# master.net
KiCad netlist of a schematic drawn in Altium Designer
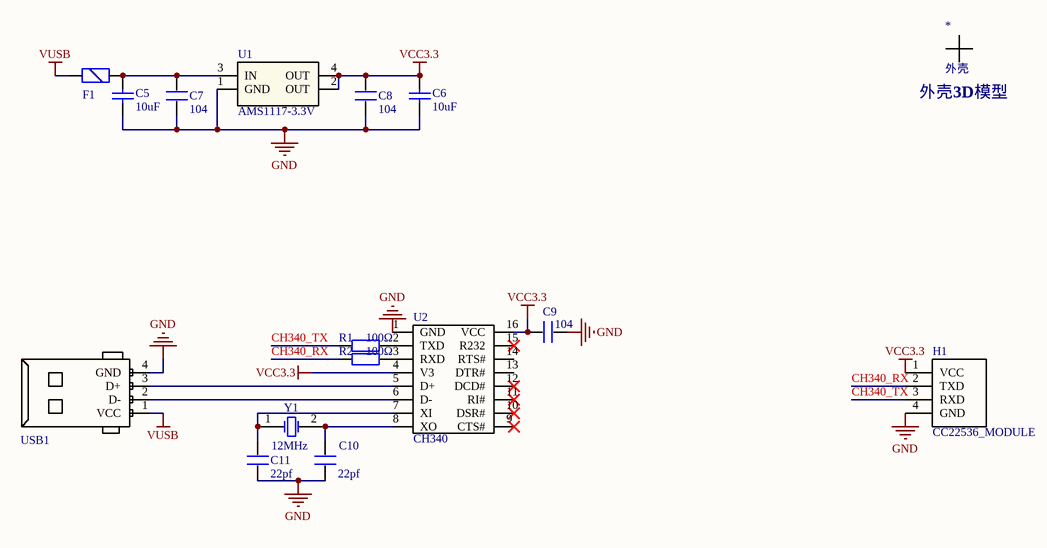
[diagram p0: master.SchDoc]

(export (version "E")
  (design (tool "Eeschema 10.0.6"))
  (components
    (comp (ref "*") (value "外壳") (footprint "MYLIB:接收端外壳") (libsource (lib "mylib") (part "外壳")))
    (comp (ref "C5")
      (value "10uF")
      (footprint "0805_C")
      (description "贴片电容")
      (libsource (lib "嘉立创库") (part "0805 2.2uF (225) 20% 50V"))
    )
    (comp (ref "C6")
      (value "10uF")
      (footprint "0805_C")
      (description "贴片电容")
      (libsource (lib "嘉立创库") (part "0805 2.2uF (225) 20% 50V"))
    )
    (comp (ref "C7")
      (value "104")
      (footprint "嘉立创库:0603_C")
      (libsource (lib "WarShip V3 STM32103封装库") (part "C"))
    )
    (comp (ref "C8")
      (value "104")
      (footprint "嘉立创库:0603_C")
      (libsource (lib "WarShip V3 STM32103封装库") (part "C"))
    )
    (comp (ref "C9")
      (value "104")
      (footprint "嘉立创库:0603_C")
      (libsource (lib "WarShip V3 STM32103封装库") (part "C"))
    )
    (comp (ref "C10")
      (value "22pf")
      (footprint "嘉立创库:0603_C")
      (libsource (lib "WarShip V3 STM32103封装库") (part "C"))
    )
    (comp (ref "C11")
      (value "22pf")
      (footprint "嘉立创库:0603_C")
      (libsource (lib "WarShip V3 STM32103封装库") (part "C"))
    )
    (comp (ref "F1") (value "F1") (footprint "MYLIB:Fuse1210") (libsource (lib "mylib") (part "Fuse")))
    (comp (ref "H1")
      (value "CC22536_MODULE")
      (footprint "WARSHIP:HDR1X4")
      (libsource (lib "mylib") (part "CC22536_MODULE"))
    )
    (comp (ref "R1")
      (value "100Ω")
      (footprint "0603_R")
      (description "贴片电阻")
      (libsource (lib "嘉立创库") (part "0603 1.1KΩ (1101) 1%"))
    )
    (comp (ref "R2")
      (value "100Ω")
      (footprint "0603_R")
      (description "贴片电阻")
      (libsource (lib "嘉立创库") (part "0603 1.1KΩ (1101) 1%"))
    )
    (comp (ref "U1")
      (value "AMS1117-3.3V")
      (footprint "AMS1117_S0T89")
      (libsource (lib "mylib") (part "AMS1117"))
    )
    (comp (ref "U2") (value "CH340") (footprint "3D common:SOP16") (libsource (lib "mylib") (part "CH340")))
    (comp (ref "USB1") (value "USB") (footprint "MYLIB:USB-211") (libsource (lib "mylib") (part "USB公头A")))
    (comp (ref "Y1")
      (value "12MHz")
      (footprint "3D_1:XTAL-49/S_N")
      (description "Crystal Oscillator")
      (fields (field (name "PUBLISHER") "Altium Limited"))
      (libsource (lib "WarShip V3 STM32103封装库") (part "XTAL"))
    )
  )
  (nets
    (net (code "1") (name "/CH340_RX") (class "Default")
      (node (ref "H1") (pin "2") (pinfunction "TXD_2") (pintype "passive"))
      (node (ref "R2") (pin "2") (pinfunction "2_2") (pintype "passive"))
    )
    (net (code "2") (name "/CH340_TX") (class "Default")
      (node (ref "H1") (pin "3") (pinfunction "RXD_3") (pintype "passive"))
      (node (ref "R1") (pin "2") (pinfunction "2_2") (pintype "passive"))
    )
    (net (code "3") (name "GND") (class "Default")
      (node (ref "C10") (pin "2") (pintype "passive"))
      (node (ref "C11") (pin "1") (pintype "passive"))
      (node (ref "C5") (pin "1") (pinfunction "1_1") (pintype "passive"))
      (node (ref "C6") (pin "1") (pinfunction "1_1") (pintype "passive"))
      (node (ref "C7") (pin "2") (pintype "passive"))
      (node (ref "C8") (pin "2") (pintype "passive"))
      (node (ref "C9") (pin "1") (pintype "passive"))
      (node (ref "H1") (pin "4") (pinfunction "GND_4") (pintype "passive"))
      (node (ref "U1") (pin "1") (pinfunction "GND_1") (pintype "passive"))
      (node (ref "U2") (pin "1") (pinfunction "GND_1") (pintype "passive"))
      (node (ref "USB1") (pin "4") (pinfunction "GND_4") (pintype "passive"))
    )
    (net (code "4") (name "Net-(U1-IN)") (class "Default")
      (node (ref "C5") (pin "2") (pinfunction "2_2") (pintype "passive"))
      (node (ref "C7") (pin "1") (pintype "passive"))
      (node (ref "F1") (pin "1") (pinfunction "1_1") (pintype "passive"))
      (node (ref "U1") (pin "3") (pinfunction "IN_3") (pintype "passive"))
    )
    (net (code "5") (name "Net-(U2-D+)") (class "Default")
      (node (ref "U2") (pin "5") (pinfunction "D+_5") (pintype "passive"))
      (node (ref "USB1") (pin "3") (pinfunction "D+_3") (pintype "passive"))
    )
    (net (code "6") (name "Net-(U2-D-)") (class "Default")
      (node (ref "U2") (pin "6") (pinfunction "D-_6") (pintype "passive"))
      (node (ref "USB1") (pin "2") (pinfunction "D-_2") (pintype "passive"))
    )
    (net (code "7") (name "Net-(U2-RXD)") (class "Default")
      (node (ref "R2") (pin "1") (pinfunction "1_1") (pintype "passive"))
      (node (ref "U2") (pin "3") (pinfunction "RXD_3") (pintype "passive"))
    )
    (net (code "8") (name "Net-(U2-TXD)") (class "Default")
      (node (ref "R1") (pin "1") (pinfunction "1_1") (pintype "passive"))
      (node (ref "U2") (pin "2") (pinfunction "TXD_2") (pintype "passive"))
    )
    (net (code "9") (name "Net-(U2-XI)") (class "Default")
      (node (ref "C11") (pin "2") (pintype "passive"))
      (node (ref "U2") (pin "7") (pinfunction "XI_7") (pintype "passive"))
      (node (ref "Y1") (pin "1") (pinfunction "OSC1_1") (pintype "passive"))
    )
    (net (code "10") (name "Net-(U2-XO)") (class "Default")
      (node (ref "C10") (pin "1") (pintype "passive"))
      (node (ref "U2") (pin "8") (pinfunction "XO_8") (pintype "passive"))
      (node (ref "Y1") (pin "2") (pinfunction "OSC2_2") (pintype "passive"))
    )
    (net (code "11") (name "VCC3.3") (class "Default")
      (node (ref "C6") (pin "2") (pinfunction "2_2") (pintype "passive"))
      (node (ref "C8") (pin "1") (pintype "passive"))
      (node (ref "C9") (pin "2") (pintype "passive"))
      (node (ref "H1") (pin "1") (pinfunction "VCC_1") (pintype "passive"))
      (node (ref "U1") (pin "2") (pinfunction "OUT_2") (pintype "passive"))
      (node (ref "U1") (pin "4") (pinfunction "OUT_4") (pintype "passive"))
      (node (ref "U2") (pin "16") (pinfunction "VCC_16") (pintype "passive"))
      (node (ref "U2") (pin "4") (pinfunction "V3_4") (pintype "passive"))
    )
    (net (code "12") (name "VUSB") (class "Default")
      (node (ref "F1") (pin "2") (pinfunction "2_2") (pintype "passive"))
      (node (ref "USB1") (pin "1") (pinfunction "VCC_1") (pintype "passive"))
    )
    (net (code "13") (name "unconnected-(U2-CTS#-Pad9)") (class "Default")
      (node (ref "U2") (pin "9") (pinfunction "CTS#_9") (pintype "passive+no_connect"))
    )
    (net (code "14") (name "unconnected-(U2-DCD#-Pad12)") (class "Default")
      (node (ref "U2") (pin "12") (pinfunction "DCD#_12") (pintype "passive+no_connect"))
    )
    (net (code "15") (name "unconnected-(U2-DSR#-Pad10)") (class "Default")
      (node (ref "U2") (pin "10") (pinfunction "DSR#_10") (pintype "passive+no_connect"))
    )
    (net (code "16") (name "unconnected-(U2-DTR#-Pad13)") (class "Default")
      (node (ref "U2") (pin "13") (pinfunction "DTR#_13") (pintype "passive"))
    )
    (net (code "17") (name "unconnected-(U2-R232-Pad15)") (class "Default")
      (node (ref "U2") (pin "15") (pinfunction "R232_15") (pintype "passive+no_connect"))
    )
    (net (code "18") (name "unconnected-(U2-RI#-Pad11)") (class "Default")
      (node (ref "U2") (pin "11") (pinfunction "RI#_11") (pintype "passive+no_connect"))
    )
    (net (code "19") (name "unconnected-(U2-RTS#-Pad14)") (class "Default")
      (node (ref "U2") (pin "14") (pinfunction "RTS#_14") (pintype "passive"))
    )
  )
)
